# oneKey_2020.net
KiCad netlist of a schematic drawn in EAGLE
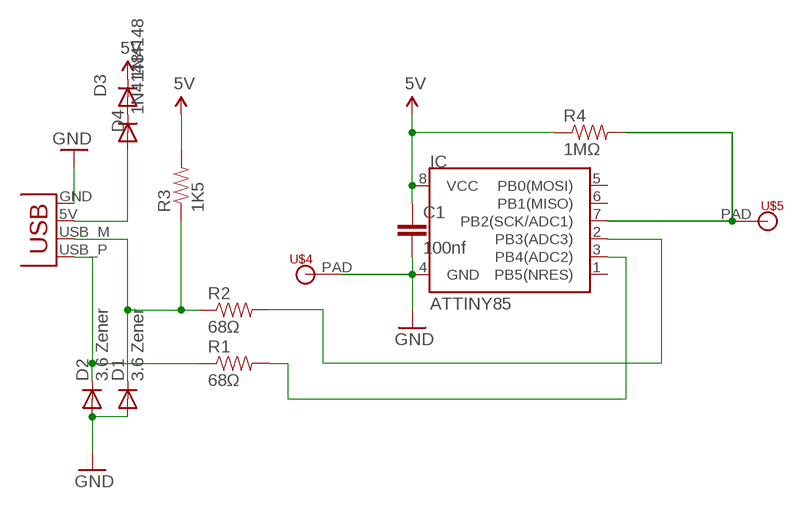
[diagram p0: schematic, sheet 1]

(export (version "E")
  (design (tool "Eeschema 10.0.6"))
  (components
    (comp (ref "C1")
      (value "100nf")
      (footprint "eagle-import:CAP-PTH-SMALL-KIT")
      (libsource (lib "eagle-import") (part "CAPKIT"))
    )
    (comp (ref "D1")
      (value "3.6 Zener")
      (footprint "eagle-import:DO35-10")
      (libsource (lib "eagle-import") (part "1N4148"))
    )
    (comp (ref "D2")
      (value "3.6 Zener")
      (footprint "eagle-import:DO35-10")
      (libsource (lib "eagle-import") (part "1N4148"))
    )
    (comp (ref "D3")
      (value "1N4148")
      (footprint "eagle-import:DO35-10")
      (libsource (lib "eagle-import") (part "1N4148"))
    )
    (comp (ref "D4")
      (value "1N4148")
      (footprint "eagle-import:DO35-10")
      (libsource (lib "eagle-import") (part "1N4148"))
    )
    (comp (ref "IC")
      (value "ATTINY85")
      (footprint "eagle-import:DIP08")
      (libsource (lib "eagle-import") (part "ATTINY45DIP8"))
    )
    (comp (ref "R1")
      (value "68Ω")
      (footprint "eagle-import:AXIAL-0.3")
      (libsource (lib "eagle-import") (part "RESISTORAXIAL-0.3"))
    )
    (comp (ref "R2")
      (value "68Ω")
      (footprint "eagle-import:AXIAL-0.3")
      (libsource (lib "eagle-import") (part "RESISTORAXIAL-0.3"))
    )
    (comp (ref "R3")
      (value "1K5")
      (footprint "eagle-import:AXIAL-0.3")
      (libsource (lib "eagle-import") (part "RESISTORAXIAL-0.3"))
    )
    (comp (ref "R4")
      (value "1MΩ")
      (footprint "eagle-import:AXIAL-0.3")
      (libsource (lib "eagle-import") (part "RESISTORAXIAL-0.3"))
    )
    (comp (ref "U$4")
      (value "MICROBIT_PAD")
      (footprint "eagle-import:MICROBIT_PAD")
      (libsource (lib "eagle-import") (part "MICROBIT_PAD"))
    )
    (comp (ref "U$5")
      (value "MICROBIT_PAD")
      (footprint "eagle-import:MICROBIT_PAD")
      (libsource (lib "eagle-import") (part "MICROBIT_PAD"))
    )
    (comp (ref "X1")
      (value "USBPCB")
      (footprint "eagle-import:USB-A-PCB")
      (libsource (lib "eagle-import") (part "USBPCB"))
    )
  )
  (nets
    (net (code "1") (name "5V") (class "Default")
      (node (ref "C1") (pin "1") (pinfunction "1_1") (pintype "passive"))
      (node (ref "D3") (pin "C") (pinfunction "C_C") (pintype "passive"))
      (node (ref "IC") (pin "8") (pinfunction "VCC_8") (pintype "bidirectional"))
      (node (ref "R3") (pin "P$2") (pinfunction "2_P$2") (pintype "passive"))
      (node (ref "R4") (pin "P$1") (pinfunction "1_P$1") (pintype "passive"))
    )
    (net (code "2") (name "GND") (class "Default")
      (node (ref "C1") (pin "2") (pinfunction "2_2") (pintype "passive"))
      (node (ref "D1") (pin "A") (pinfunction "A_A") (pintype "passive"))
      (node (ref "D2") (pin "A") (pinfunction "A_A") (pintype "passive"))
      (node (ref "IC") (pin "4") (pinfunction "GND_4") (pintype "bidirectional"))
      (node (ref "U$4") (pin "PAD") (pinfunction "P$1_PAD") (pintype "bidirectional"))
      (node (ref "X1") (pin "GND") (pinfunction "GND_GND") (pintype "bidirectional"))
    )
    (net (code "3") (name "Net-(D3-PadA)") (class "Default")
      (node (ref "D3") (pin "A") (pinfunction "A_A") (pintype "passive"))
      (node (ref "D4") (pin "C") (pinfunction "C_C") (pintype "passive"))
    )
    (net (code "4") (name "Net-(IC-PB2(SCK{slash}ADC1))") (class "Default")
      (node (ref "IC") (pin "7") (pinfunction "PB2(SCK/ADC1)_7") (pintype "bidirectional"))
      (node (ref "R4") (pin "P$2") (pinfunction "2_P$2") (pintype "passive"))
      (node (ref "U$5") (pin "PAD") (pinfunction "P$1_PAD") (pintype "bidirectional"))
    )
    (net (code "5") (name "Net-(IC-PB3(ADC3))") (class "Default")
      (node (ref "IC") (pin "2") (pinfunction "PB3(ADC3)_2") (pintype "bidirectional"))
      (node (ref "R2") (pin "P$2") (pinfunction "2_P$2") (pintype "passive"))
    )
    (net (code "6") (name "Net-(IC-PB4(ADC2))") (class "Default")
      (node (ref "IC") (pin "3") (pinfunction "PB4(ADC2)_3") (pintype "bidirectional"))
      (node (ref "R1") (pin "P$2") (pinfunction "2_P$2") (pintype "passive"))
    )
    (net (code "7") (name "Net-(R1-1)") (class "Default")
      (node (ref "D2") (pin "C") (pinfunction "C_C") (pintype "passive"))
      (node (ref "R1") (pin "P$1") (pinfunction "1_P$1") (pintype "passive"))
      (node (ref "X1") (pin "USB_P") (pinfunction "D+_USB_P") (pintype "bidirectional"))
    )
    (net (code "8") (name "Net-(R2-1)") (class "Default")
      (node (ref "D1") (pin "C") (pinfunction "C_C") (pintype "passive"))
      (node (ref "R2") (pin "P$1") (pinfunction "1_P$1") (pintype "passive"))
      (node (ref "R3") (pin "P$1") (pinfunction "1_P$1") (pintype "passive"))
      (node (ref "X1") (pin "USB_M") (pinfunction "D-_USB_M") (pintype "bidirectional"))
    )
    (net (code "9") (name "Net-(X1-VBUS)") (class "Default")
      (node (ref "D4") (pin "A") (pinfunction "A_A") (pintype "passive"))
      (node (ref "X1") (pin "5V") (pinfunction "VBUS_5V") (pintype "bidirectional"))
    )
    (net (code "10") (name "unconnected-(IC-PB0(MOSI)-Pad5)") (class "Default")
      (node (ref "IC") (pin "5") (pinfunction "PB0(MOSI)_5") (pintype "bidirectional"))
    )
    (net (code "11") (name "unconnected-(IC-PB1(MISO)-Pad6)") (class "Default")
      (node (ref "IC") (pin "6") (pinfunction "PB1(MISO)_6") (pintype "bidirectional"))
    )
    (net (code "12") (name "unconnected-(IC-PB5(NRES)-Pad1)") (class "Default")
      (node (ref "IC") (pin "1") (pinfunction "PB5(NRES)_1") (pintype "bidirectional"))
    )
  )
)
